# oLoRa-part-power.net
KiCad netlist of a schematic drawn in EasyEDA
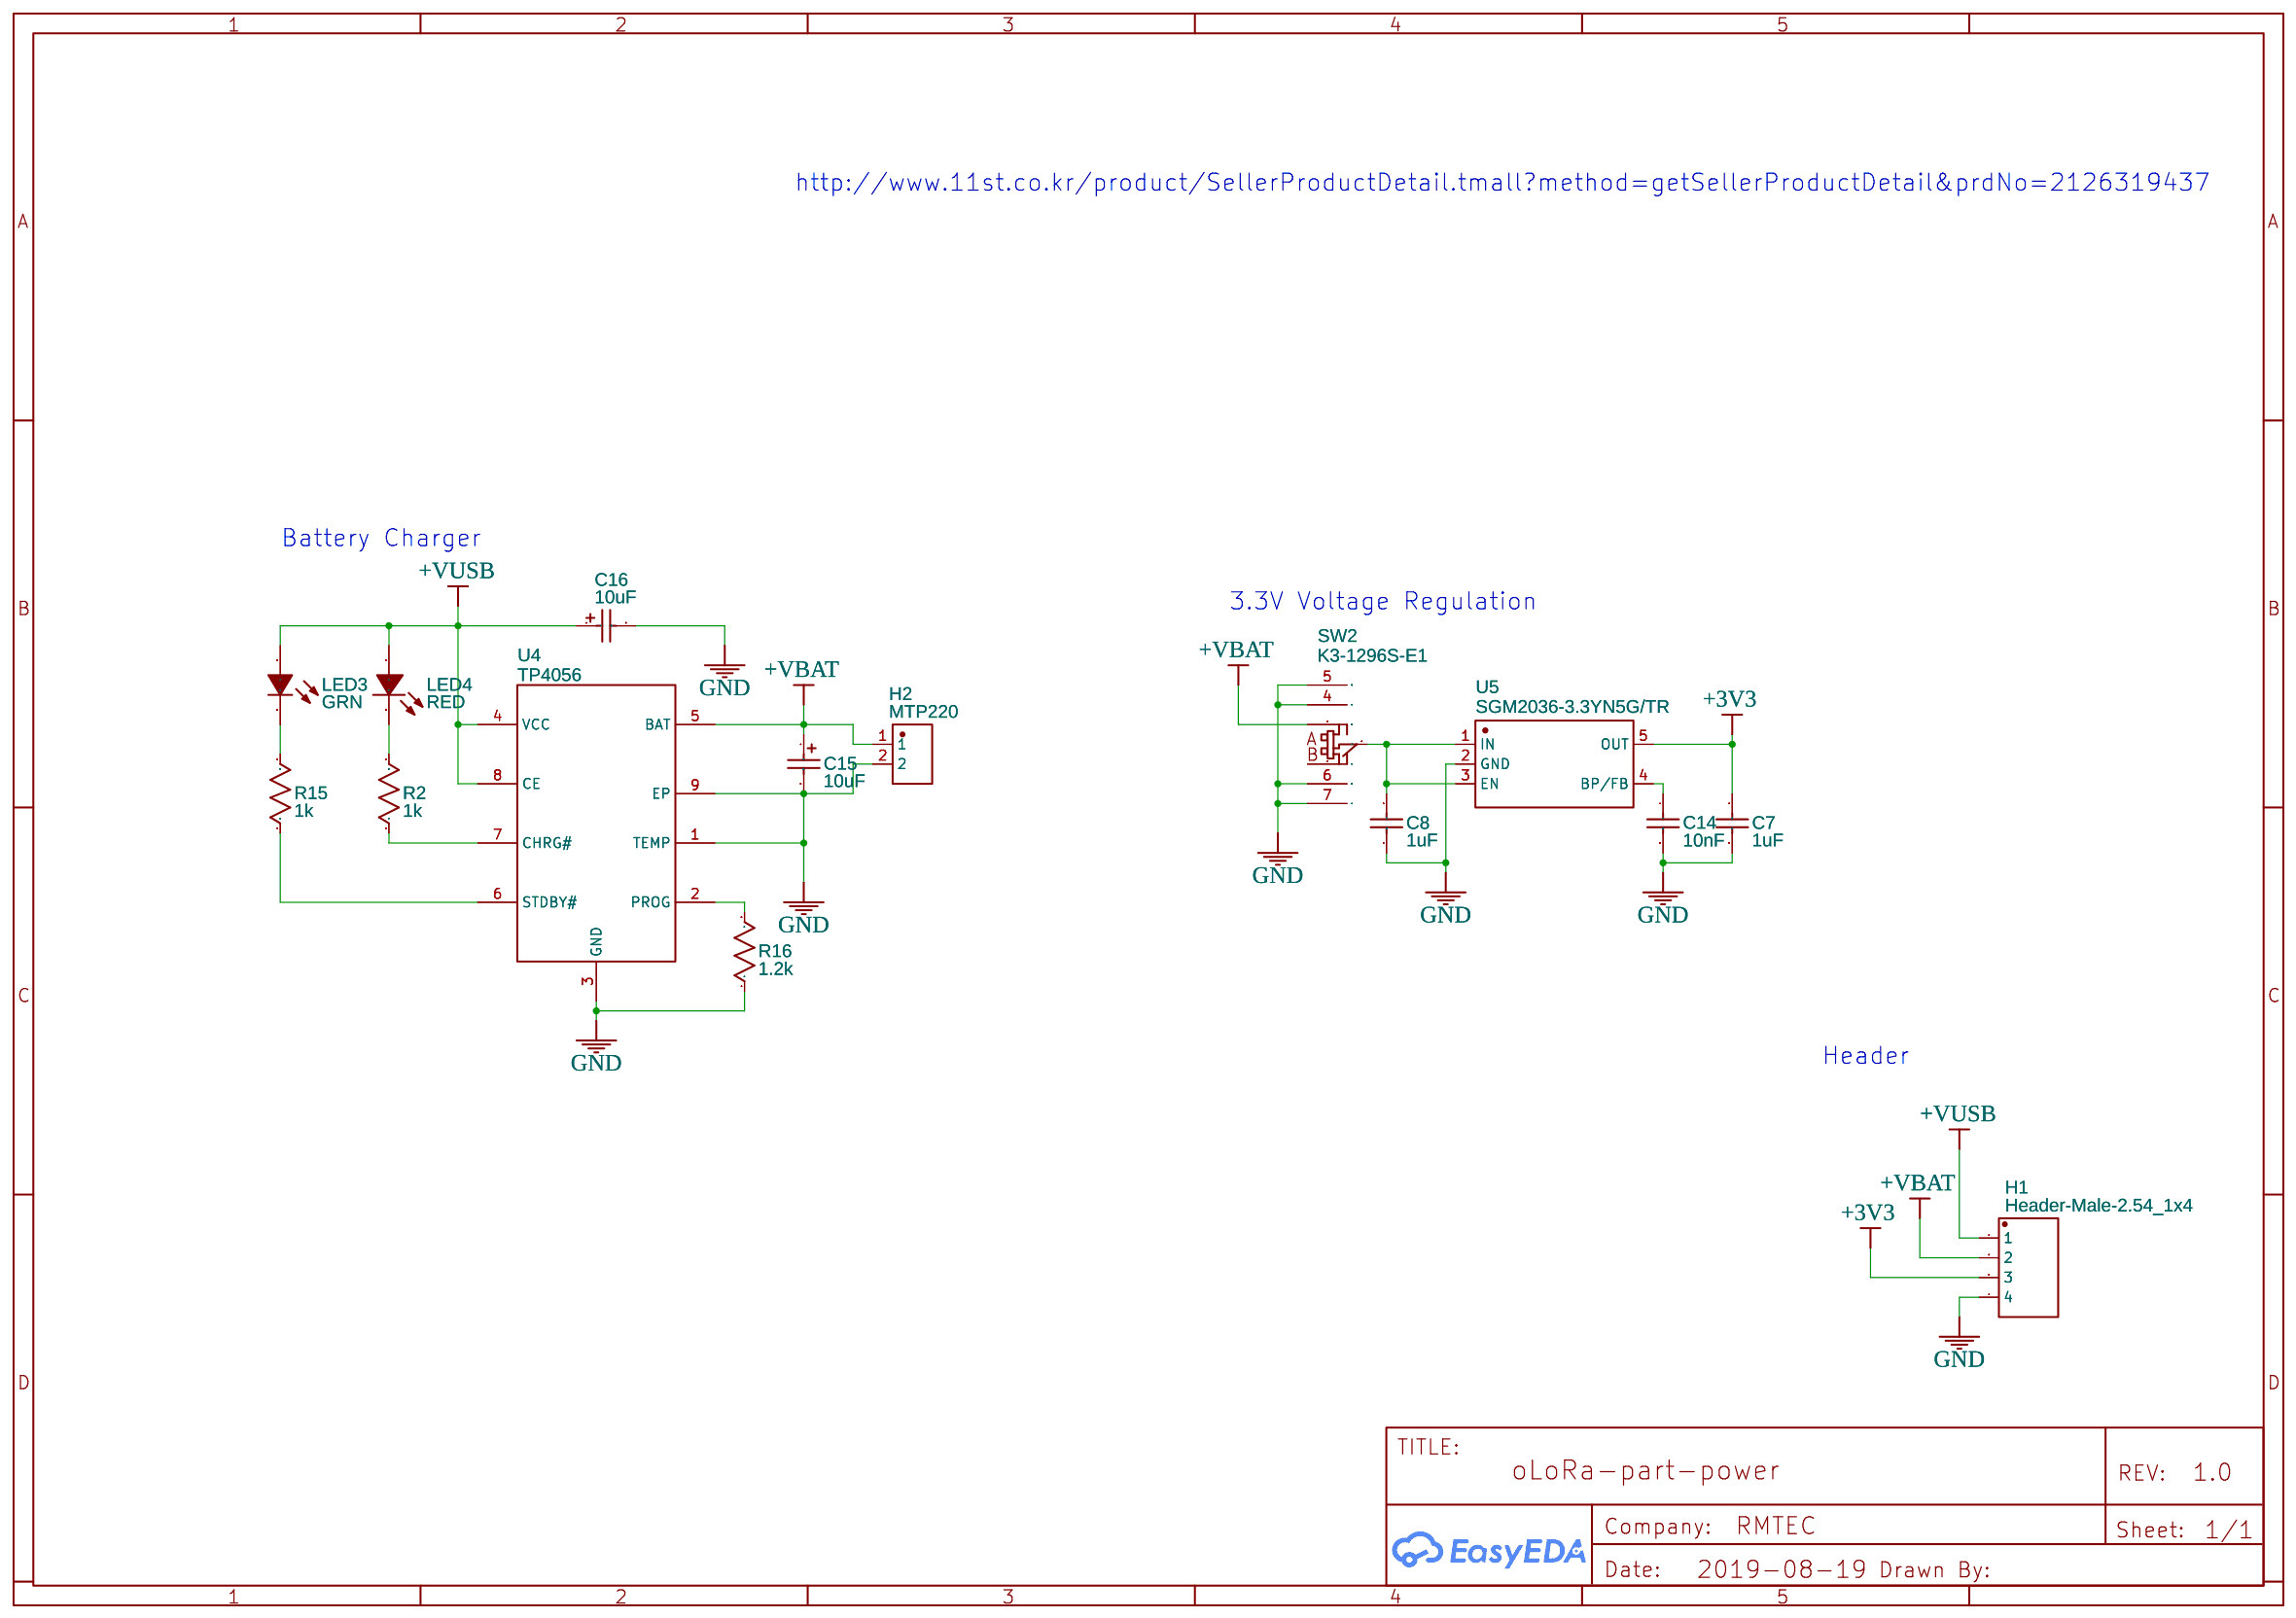
[diagram p0: schematic sheet]

(export (version "E")
  (design (tool "Eeschema 10.0.6"))
  (components
    (comp (ref "C7")
      (value "1uF")
      (fields
        (field (name "BOM_Manufacturer Part") "CL10B105KQ8NNNC")
        (field (name "BOM_Supplier Part") "C105524")
      )
      (libsource (lib "") (part "CL10B105KQ8NNNC"))
    )
    (comp (ref "C8")
      (value "1uF")
      (fields
        (field (name "BOM_Manufacturer Part") "CL10B105KQ8NNNC")
        (field (name "BOM_Supplier Part") "C105524")
      )
      (libsource (lib "") (part "CL10B105KQ8NNNC"))
    )
    (comp (ref "C14")
      (value "10nF")
      (fields
        (field (name "BOM_Manufacturer Part") "CGA3E2C0G1H103JT0Y0N")
        (field (name "BOM_Supplier Part") "C76710")
      )
      (libsource (lib "") (part "CGA3E2C0G1H103JT0Y0N"))
    )
    (comp (ref "C15")
      (value "10uF")
      (fields
        (field (name "BOM_Manufacturer Part") "TAJA106K016RNJ")
        (field (name "BOM_Supplier Part") "C7171")
      )
      (libsource (lib "") (part "TAJA106K016RNJ"))
    )
    (comp (ref "C16")
      (value "10uF")
      (fields
        (field (name "BOM_Manufacturer Part") "TAJA106K016RNJ")
        (field (name "BOM_Supplier Part") "C7171")
      )
      (libsource (lib "") (part "TAJA106K016RNJ_1"))
    )
    (comp (ref "H1")
      (value "Header-Male-2.54_1x4")
      (fields
        (field (name "BOM_Manufacturer Part") "210S-1*4P L=11.6MMGold-plated black")
        (field (name "BOM_Supplier Part") "C124378")
      )
      (libsource (lib "") (part "Unknown_1015_635"))
    )
    (comp (ref "H2")
      (value "MTP220")
      (fields
        (field (name "BOM_Manufacturer Part") "MTP220-1102R1")
        (field (name "BOM_Supplier Part") "C376096")
      )
      (libsource (lib "") (part "Unknown_455_375"))
    )
    (comp (ref "LED3")
      (value "GRN")
      (fields
        (field (name "BOM_Manufacturer Part") "19-217/GHC-YR1S2/3T")
        (field (name "BOM_Supplier Part") "C72043")
      )
      (libsource (lib "") (part "Unknown_140_340"))
    )
    (comp (ref "LED4")
      (value "RED")
      (fields (field (name "BOM_Manufacturer Part") "KT-0603R") (field (name "BOM_Supplier Part") "C2286"))
      (libsource (lib "") (part "Unknown_195_340"))
    )
    (comp (ref "R2") (value "1k") (libsource (lib "") (part "Res_0603(1/10W)_US")))
    (comp (ref "R15") (value "1k") (libsource (lib "") (part "Res_0603(1/10W)_US")))
    (comp (ref "R16") (value "1.2k") (libsource (lib "") (part "Res_0603(1/10W)_US")))
    (comp (ref "SW2")
      (value "K3-1296S-E1")
      (fields (field (name "BOM_Supplier Part") "C128955"))
      (libsource (lib "") (part "Unknown_670_370"))
    )
    (comp (ref "U4")
      (value "TP4056")
      (fields (field (name "BOM_Supplier Part") "C16581"))
      (libsource (lib "") (part "Unknown_295_420"))
    )
    (comp (ref "U5")
      (value "SGM2036-3.3YN5G/TR")
      (fields (field (name "BOM_Supplier Part") "C92402"))
      (libsource (lib "") (part "Unknown_780_380"))
    )
  )
  (nets
    (net (code "1") (name "+3V3") (class "Default")
      (node (ref "C7") (pin "2") (pinfunction "2_2") (pintype "input"))
      (node (ref "H1") (pin "3") (pinfunction "3_3") (pintype "unspecified"))
      (node (ref "U5") (pin "5") (pinfunction "OUT_5") (pintype "unspecified"))
    )
    (net (code "2") (name "+VBAT") (class "Default")
      (node (ref "C15") (pin "1") (pinfunction "1_1") (pintype "input"))
      (node (ref "H1") (pin "2") (pinfunction "2_2") (pintype "unspecified"))
      (node (ref "H2") (pin "1") (pinfunction "1_1") (pintype "unspecified"))
      (node (ref "SW2") (pin "3") (pinfunction "3_3") (pintype "unspecified"))
      (node (ref "U4") (pin "5") (pinfunction "BAT_5") (pintype "unspecified"))
    )
    (net (code "3") (name "+VUSB") (class "Default")
      (node (ref "C16") (pin "1") (pinfunction "1_1") (pintype "input"))
      (node (ref "H1") (pin "1") (pinfunction "1_1") (pintype "unspecified"))
      (node (ref "LED3") (pin "1") (pinfunction "A_1") (pintype "input"))
      (node (ref "LED4") (pin "1") (pinfunction "A_1") (pintype "unspecified"))
      (node (ref "U4") (pin "4") (pinfunction "VCC_4") (pintype "unspecified"))
      (node (ref "U4") (pin "8") (pinfunction "CE_8") (pintype "unspecified"))
    )
    (net (code "4") (name "GND") (class "Default")
      (node (ref "C14") (pin "2") (pinfunction "2_2") (pintype "input"))
      (node (ref "C15") (pin "2") (pinfunction "2_2") (pintype "input"))
      (node (ref "C16") (pin "2") (pinfunction "2_2") (pintype "input"))
      (node (ref "C7") (pin "1") (pinfunction "1_1") (pintype "input"))
      (node (ref "C8") (pin "1") (pinfunction "1_1") (pintype "input"))
      (node (ref "H1") (pin "4") (pinfunction "4_4") (pintype "unspecified"))
      (node (ref "H2") (pin "2") (pinfunction "2_2") (pintype "unspecified"))
      (node (ref "R16") (pin "1") (pinfunction "1_1") (pintype "unspecified"))
      (node (ref "SW2") (pin "4") (pinfunction "4_4") (pintype "unspecified"))
      (node (ref "SW2") (pin "5") (pinfunction "5_5") (pintype "unspecified"))
      (node (ref "SW2") (pin "6") (pinfunction "6_6") (pintype "unspecified"))
      (node (ref "SW2") (pin "7") (pinfunction "7_7") (pintype "unspecified"))
      (node (ref "U4") (pin "1") (pinfunction "TEMP_1") (pintype "unspecified"))
      (node (ref "U4") (pin "3") (pinfunction "GND_3") (pintype "unspecified"))
      (node (ref "U4") (pin "9") (pinfunction "EP_9") (pintype "unspecified"))
      (node (ref "U5") (pin "2") (pinfunction "GND_2") (pintype "unspecified"))
    )
    (net (code "5") (name "Net-(LED3-C)") (class "Default")
      (node (ref "LED3") (pin "2") (pinfunction "C_2") (pintype "input"))
      (node (ref "R15") (pin "2") (pinfunction "2_2") (pintype "unspecified"))
    )
    (net (code "6") (name "Net-(LED4-K)") (class "Default")
      (node (ref "LED4") (pin "2") (pinfunction "K_2") (pintype "unspecified"))
      (node (ref "R2") (pin "2") (pinfunction "2_2") (pintype "unspecified"))
    )
    (net (code "7") (name "Net-(U4-CHRG#)") (class "Default")
      (node (ref "R2") (pin "1") (pinfunction "1_1") (pintype "unspecified"))
      (node (ref "U4") (pin "7") (pinfunction "CHRG#_7") (pintype "unspecified"))
    )
    (net (code "8") (name "Net-(U4-PROG)") (class "Default")
      (node (ref "R16") (pin "2") (pinfunction "2_2") (pintype "unspecified"))
      (node (ref "U4") (pin "2") (pinfunction "PROG_2") (pintype "unspecified"))
    )
    (net (code "9") (name "Net-(U4-STDBY#)") (class "Default")
      (node (ref "R15") (pin "1") (pinfunction "1_1") (pintype "unspecified"))
      (node (ref "U4") (pin "6") (pinfunction "STDBY#_6") (pintype "unspecified"))
    )
    (net (code "10") (name "Net-(U5-BP{slash}FB)") (class "Default")
      (node (ref "C14") (pin "1") (pinfunction "1_1") (pintype "input"))
      (node (ref "U5") (pin "4") (pinfunction "BP/FB_4") (pintype "unspecified"))
    )
    (net (code "11") (name "Net-(U5-EN)") (class "Default")
      (node (ref "C8") (pin "2") (pinfunction "2_2") (pintype "input"))
      (node (ref "SW2") (pin "2") (pinfunction "2_2") (pintype "unspecified"))
      (node (ref "U5") (pin "1") (pinfunction "IN_1") (pintype "unspecified"))
      (node (ref "U5") (pin "3") (pinfunction "EN_3") (pintype "unspecified"))
    )
    (net (code "12") (name "unconnected-(SW2-Pad1)") (class "Default")
      (node (ref "SW2") (pin "1") (pinfunction "1_1") (pintype "unspecified"))
    )
  )
)
